# T15_PRI_SYS_V1_3.net
KiCad netlist of a schematic drawn in EAGLE
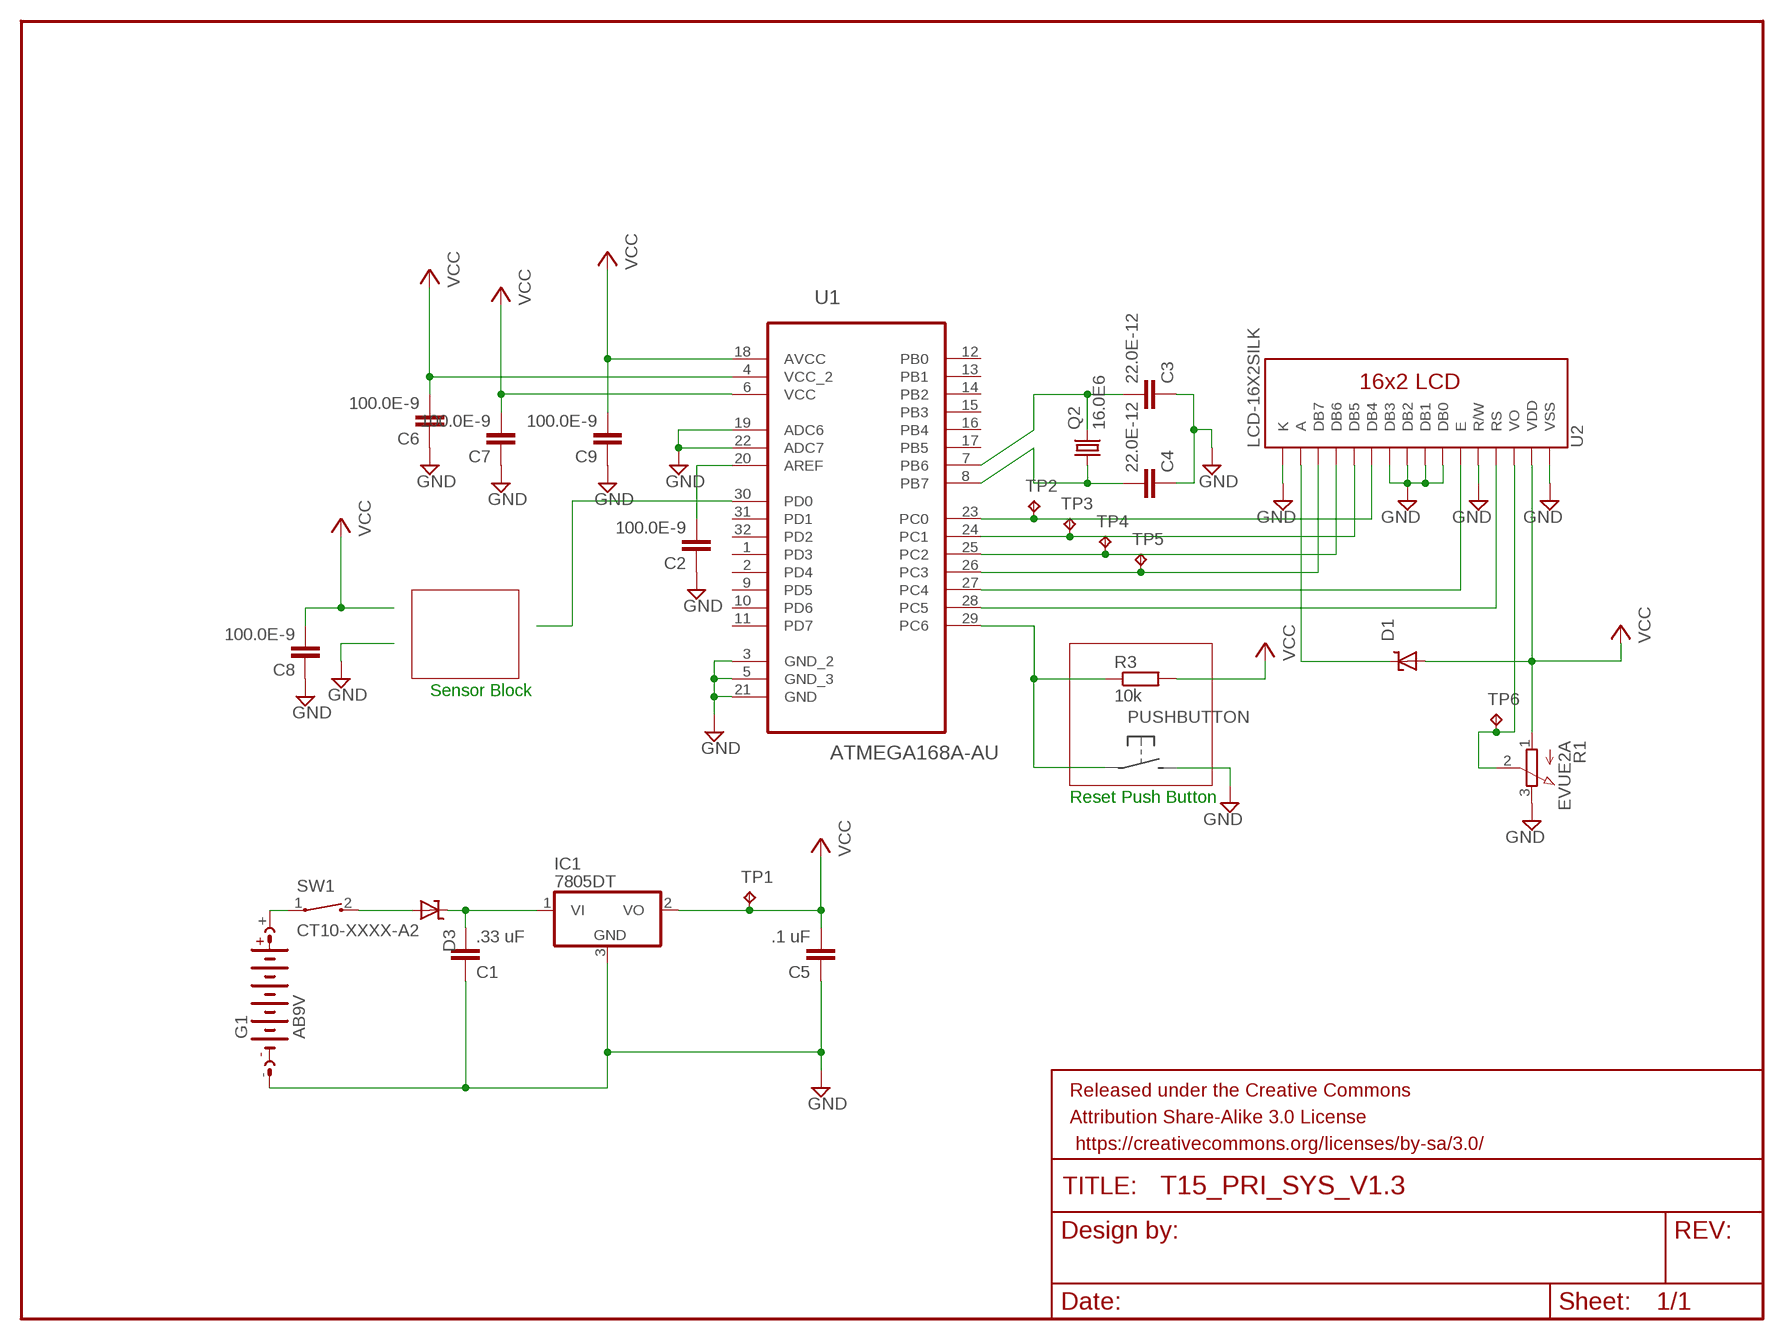
[diagram p0: schematic, sheet 1]

(export (version "E")
  (design (tool "Eeschema 10.0.6"))
  (components
    (comp (ref "C1")
      (value ".33 uF")
      (footprint "eagle-import:C025-024X044")
      (libsource (lib "eagle-import") (part "C-EU025-024X044"))
    )
    (comp (ref "C2")
      (value "100.0E-9")
      (footprint "eagle-import:C025-024X044")
      (libsource (lib "eagle-import") (part "C-EU025-024X044"))
    )
    (comp (ref "C3")
      (value "22.0E-12")
      (footprint "eagle-import:C025-024X044")
      (libsource (lib "eagle-import") (part "C-EU025-024X044"))
    )
    (comp (ref "C4")
      (value "22.0E-12")
      (footprint "eagle-import:C025-024X044")
      (libsource (lib "eagle-import") (part "C-EU025-024X044"))
    )
    (comp (ref "C5")
      (value ".1 uF")
      (footprint "eagle-import:C025-024X044")
      (libsource (lib "eagle-import") (part "C-EU025-024X044"))
    )
    (comp (ref "C6")
      (value "100.0E-9")
      (footprint "eagle-import:C025-024X044")
      (libsource (lib "eagle-import") (part "C-EU025-024X044"))
    )
    (comp (ref "C7")
      (value "100.0E-9")
      (footprint "eagle-import:C025-024X044")
      (libsource (lib "eagle-import") (part "C-EU025-024X044"))
    )
    (comp (ref "C8")
      (value "100.0E-9")
      (footprint "eagle-import:C025-024X044")
      (libsource (lib "eagle-import") (part "C-EU025-024X044"))
    )
    (comp (ref "C9")
      (value "100.0E-9")
      (footprint "eagle-import:C025-024X044")
      (libsource (lib "eagle-import") (part "C-EU025-024X044"))
    )
    (comp (ref "D1")
      (value "SUPPRESSOR-SMBJ")
      (footprint "eagle-import:SMBJ")
      (libsource (lib "eagle-import") (part "SUPPRESSOR-SMBJ"))
    )
    (comp (ref "D3")
      (value "SUPPRESSOR-SMBJ")
      (footprint "eagle-import:SMBJ")
      (libsource (lib "eagle-import") (part "SUPPRESSOR-SMBJ"))
    )
    (comp (ref "FRAME1")
      (value "FRAME-LETTER")
      (footprint "eagle-import:CREATIVE_COMMONS")
      (libsource (lib "eagle-import") (part "FRAME-LETTER"))
    )
    (comp (ref "G1")
      (value "AB9V")
      (footprint "eagle-import:AB9V")
      (libsource (lib "eagle-import") (part "AB9V"))
    )
    (comp (ref "IC1")
      (value "7805DT")
      (footprint "eagle-import:TO252")
      (libsource (lib "eagle-import") (part "78DT05"))
    )
    (comp (ref "Q2")
      (value "16.0E6")
      (footprint "eagle-import:HC49_S")
      (libsource (lib "eagle-import") (part "CRYSTALHC49S"))
    )
    (comp (ref "R1")
      (value "EVUE2A")
      (footprint "eagle-import:EVUE")
      (libsource (lib "eagle-import") (part "EVUE2A"))
    )
    (comp (ref "R3")
      (value "10k")
      (footprint "eagle-import:0204_5")
      (libsource (lib "eagle-import") (part "R-EU_0204/5"))
    )
    (comp (ref "SW1")
      (value "CT10-XXXX-A2")
      (footprint "eagle-import:CT10-XXXX-A2")
      (libsource (lib "eagle-import") (part "CT10-XXXX-A2"))
    )
    (comp (ref "TP1")
      (value "TPB1,27")
      (footprint "eagle-import:B1,27")
      (libsource (lib "eagle-import") (part "TPB1,27"))
    )
    (comp (ref "TP2")
      (value "TPB1,27")
      (footprint "eagle-import:B1,27")
      (libsource (lib "eagle-import") (part "TPB1,27"))
    )
    (comp (ref "TP3")
      (value "TPB1,27")
      (footprint "eagle-import:B1,27")
      (libsource (lib "eagle-import") (part "TPB1,27"))
    )
    (comp (ref "TP4")
      (value "TPB1,27")
      (footprint "eagle-import:B1,27")
      (libsource (lib "eagle-import") (part "TPB1,27"))
    )
    (comp (ref "TP5")
      (value "TPB1,27")
      (footprint "eagle-import:B1,27")
      (libsource (lib "eagle-import") (part "TPB1,27"))
    )
    (comp (ref "TP6")
      (value "TPB1,27")
      (footprint "eagle-import:B1,27")
      (libsource (lib "eagle-import") (part "TPB1,27"))
    )
    (comp (ref "U1")
      (value "ATMEGA168A-AU")
      (footprint "eagle-import:QFP80P900X900X120-32N")
      (libsource (lib "eagle-import") (part "ATMEGA168A-AU"))
    )
    (comp (ref "U2")
      (value "LCD-16X2SILK")
      (footprint "eagle-import:LCD-16X2")
      (libsource (lib "eagle-import") (part "LCD-16X2SILK"))
    )
  )
  (nets
    (net (code "1") (name "GND") (class "Default")
      (node (ref "C1") (pin "1") (pinfunction "1_1") (pintype "passive"))
      (node (ref "C2") (pin "1") (pinfunction "1_1") (pintype "passive"))
      (node (ref "C3") (pin "1") (pinfunction "1_1") (pintype "passive"))
      (node (ref "C4") (pin "1") (pinfunction "1_1") (pintype "passive"))
      (node (ref "C5") (pin "1") (pinfunction "1_1") (pintype "passive"))
      (node (ref "C6") (pin "1") (pinfunction "1_1") (pintype "passive"))
      (node (ref "C7") (pin "1") (pinfunction "1_1") (pintype "passive"))
      (node (ref "C8") (pin "1") (pinfunction "1_1") (pintype "passive"))
      (node (ref "C9") (pin "1") (pinfunction "1_1") (pintype "passive"))
      (node (ref "G1") (pin "-") (pinfunction "-_-") (pintype "passive"))
      (node (ref "IC1") (pin "3") (pinfunction "GND_3") (pintype "passive"))
      (node (ref "R1") (pin "3") (pinfunction "E_3") (pintype "passive"))
      (node (ref "U1") (pin "19") (pinfunction "ADC6_19") (pintype "input"))
      (node (ref "U1") (pin "21") (pinfunction "GND_21") (pintype "passive"))
      (node (ref "U1") (pin "22") (pinfunction "ADC7_22") (pintype "input"))
      (node (ref "U1") (pin "3") (pinfunction "GND_2_3") (pintype "passive"))
      (node (ref "U1") (pin "5") (pinfunction "GND_3_5") (pintype "passive"))
      (node (ref "U2") (pin "1") (pinfunction "VSS_1") (pintype "power_in"))
      (node (ref "U2") (pin "10") (pinfunction "DB3_10") (pintype "bidirectional"))
      (node (ref "U2") (pin "16") (pinfunction "K_16") (pintype "power_in"))
      (node (ref "U2") (pin "5") (pinfunction "R/W_5") (pintype "input"))
      (node (ref "U2") (pin "7") (pinfunction "DB0_7") (pintype "bidirectional"))
      (node (ref "U2") (pin "8") (pinfunction "DB1_8") (pintype "bidirectional"))
      (node (ref "U2") (pin "9") (pinfunction "DB2_9") (pintype "bidirectional"))
    )
    (net (code "2") (name "Net-(D3-PadA)") (class "Default")
      (node (ref "D3") (pin "A") (pinfunction "A_A") (pintype "passive"))
      (node (ref "SW1") (pin "2") (pinfunction "2_2") (pintype "passive"))
    )
    (net (code "3") (name "Net-(G1-Pad+)") (class "Default")
      (node (ref "G1") (pin "+") (pinfunction "+_+") (pintype "passive"))
      (node (ref "SW1") (pin "1") (pinfunction "1_1") (pintype "passive"))
    )
    (net (code "4") (name "Net-(IC1-VI)") (class "Default")
      (node (ref "C1") (pin "2") (pinfunction "2_2") (pintype "passive"))
      (node (ref "D3") (pin "C") (pinfunction "C_C") (pintype "passive"))
      (node (ref "IC1") (pin "1") (pinfunction "VI_1") (pintype "input"))
    )
    (net (code "5") (name "Net-(R1-S)") (class "Default")
      (node (ref "R1") (pin "2") (pinfunction "S_2") (pintype "passive"))
      (node (ref "TP6") (pin "TP") (pinfunction "TP_TP") (pintype "input"))
      (node (ref "U2") (pin "3") (pinfunction "VO_3") (pintype "bidirectional"))
    )
    (net (code "6") (name "Net-(U1-AREF)") (class "Default")
      (node (ref "C2") (pin "2") (pinfunction "2_2") (pintype "passive"))
      (node (ref "U1") (pin "20") (pinfunction "AREF_20") (pintype "input"))
    )
    (net (code "7") (name "Net-(U1-PB6)") (class "Default")
      (node (ref "C3") (pin "2") (pinfunction "2_2") (pintype "passive"))
      (node (ref "Q2") (pin "2") (pinfunction "2_2") (pintype "passive"))
      (node (ref "U1") (pin "7") (pinfunction "PB6_7") (pintype "bidirectional"))
    )
    (net (code "8") (name "Net-(U1-PB7)") (class "Default")
      (node (ref "C4") (pin "2") (pinfunction "2_2") (pintype "passive"))
      (node (ref "Q2") (pin "1") (pinfunction "1_1") (pintype "passive"))
      (node (ref "U1") (pin "8") (pinfunction "PB7_8") (pintype "bidirectional"))
    )
    (net (code "9") (name "Net-(U1-PC0)") (class "Default")
      (node (ref "TP2") (pin "TP") (pinfunction "TP_TP") (pintype "input"))
      (node (ref "U1") (pin "23") (pinfunction "PC0_23") (pintype "bidirectional"))
      (node (ref "U2") (pin "11") (pinfunction "DB4_11") (pintype "bidirectional"))
    )
    (net (code "10") (name "Net-(U1-PC1)") (class "Default")
      (node (ref "TP3") (pin "TP") (pinfunction "TP_TP") (pintype "input"))
      (node (ref "U1") (pin "24") (pinfunction "PC1_24") (pintype "bidirectional"))
      (node (ref "U2") (pin "12") (pinfunction "DB5_12") (pintype "bidirectional"))
    )
    (net (code "11") (name "Net-(U1-PC2)") (class "Default")
      (node (ref "TP4") (pin "TP") (pinfunction "TP_TP") (pintype "input"))
      (node (ref "U1") (pin "25") (pinfunction "PC2_25") (pintype "bidirectional"))
      (node (ref "U2") (pin "13") (pinfunction "DB6_13") (pintype "bidirectional"))
    )
    (net (code "12") (name "Net-(U1-PC3)") (class "Default")
      (node (ref "TP5") (pin "TP") (pinfunction "TP_TP") (pintype "input"))
      (node (ref "U1") (pin "26") (pinfunction "PC3_26") (pintype "bidirectional"))
      (node (ref "U2") (pin "14") (pinfunction "DB7_14") (pintype "bidirectional"))
    )
    (net (code "13") (name "Net-(U1-PC4)") (class "Default")
      (node (ref "U1") (pin "27") (pinfunction "PC4_27") (pintype "bidirectional"))
      (node (ref "U2") (pin "6") (pinfunction "E_6") (pintype "input"))
    )
    (net (code "14") (name "Net-(U1-PC5)") (class "Default")
      (node (ref "U1") (pin "28") (pinfunction "PC5_28") (pintype "bidirectional"))
      (node (ref "U2") (pin "4") (pinfunction "RS_4") (pintype "input"))
    )
    (net (code "15") (name "Net-(U1-PC6)") (class "Default")
      (node (ref "R3") (pin "1") (pinfunction "1_1") (pintype "passive"))
      (node (ref "U1") (pin "29") (pinfunction "PC6_29") (pintype "bidirectional"))
    )
    (net (code "16") (name "Net-(U2-A)") (class "Default")
      (node (ref "D1") (pin "C") (pinfunction "C_C") (pintype "passive"))
      (node (ref "U2") (pin "15") (pinfunction "A_15") (pintype "power_in"))
    )
    (net (code "17") (name "VCC") (class "Default")
      (node (ref "C5") (pin "2") (pinfunction "2_2") (pintype "passive"))
      (node (ref "C6") (pin "2") (pinfunction "2_2") (pintype "passive"))
      (node (ref "C7") (pin "2") (pinfunction "2_2") (pintype "passive"))
      (node (ref "C8") (pin "2") (pinfunction "2_2") (pintype "passive"))
      (node (ref "C9") (pin "2") (pinfunction "2_2") (pintype "passive"))
      (node (ref "D1") (pin "A") (pinfunction "A_A") (pintype "passive"))
      (node (ref "IC1") (pin "2") (pinfunction "VO_2") (pintype "passive"))
      (node (ref "R1") (pin "1") (pinfunction "A_1") (pintype "passive"))
      (node (ref "R3") (pin "2") (pinfunction "2_2") (pintype "passive"))
      (node (ref "TP1") (pin "TP") (pinfunction "TP_TP") (pintype "input"))
      (node (ref "U1") (pin "18") (pinfunction "AVCC_18") (pintype "power_in"))
      (node (ref "U1") (pin "4") (pinfunction "VCC_2_4") (pintype "power_in"))
      (node (ref "U1") (pin "6") (pinfunction "VCC_6") (pintype "power_in"))
      (node (ref "U2") (pin "2") (pinfunction "VDD_2") (pintype "power_in"))
    )
    (net (code "18") (name "unconnected-(U1-PB0-Pad12)") (class "Default")
      (node (ref "U1") (pin "12") (pinfunction "PB0_12") (pintype "bidirectional"))
    )
    (net (code "19") (name "unconnected-(U1-PB1-Pad13)") (class "Default")
      (node (ref "U1") (pin "13") (pinfunction "PB1_13") (pintype "bidirectional"))
    )
    (net (code "20") (name "unconnected-(U1-PB2-Pad14)") (class "Default")
      (node (ref "U1") (pin "14") (pinfunction "PB2_14") (pintype "bidirectional"))
    )
    (net (code "21") (name "unconnected-(U1-PB3-Pad15)") (class "Default")
      (node (ref "U1") (pin "15") (pinfunction "PB3_15") (pintype "bidirectional"))
    )
    (net (code "22") (name "unconnected-(U1-PB4-Pad16)") (class "Default")
      (node (ref "U1") (pin "16") (pinfunction "PB4_16") (pintype "bidirectional"))
    )
    (net (code "23") (name "unconnected-(U1-PB5-Pad17)") (class "Default")
      (node (ref "U1") (pin "17") (pinfunction "PB5_17") (pintype "bidirectional"))
    )
    (net (code "24") (name "unconnected-(U1-PD0-Pad30)") (class "Default")
      (node (ref "U1") (pin "30") (pinfunction "PD0_30") (pintype "bidirectional"))
    )
    (net (code "25") (name "unconnected-(U1-PD1-Pad31)") (class "Default")
      (node (ref "U1") (pin "31") (pinfunction "PD1_31") (pintype "bidirectional"))
    )
    (net (code "26") (name "unconnected-(U1-PD2-Pad32)") (class "Default")
      (node (ref "U1") (pin "32") (pinfunction "PD2_32") (pintype "bidirectional"))
    )
    (net (code "27") (name "unconnected-(U1-PD3-Pad1)") (class "Default")
      (node (ref "U1") (pin "1") (pinfunction "PD3_1") (pintype "bidirectional"))
    )
    (net (code "28") (name "unconnected-(U1-PD4-Pad2)") (class "Default")
      (node (ref "U1") (pin "2") (pinfunction "PD4_2") (pintype "bidirectional"))
    )
    (net (code "29") (name "unconnected-(U1-PD5-Pad9)") (class "Default")
      (node (ref "U1") (pin "9") (pinfunction "PD5_9") (pintype "bidirectional"))
    )
    (net (code "30") (name "unconnected-(U1-PD6-Pad10)") (class "Default")
      (node (ref "U1") (pin "10") (pinfunction "PD6_10") (pintype "bidirectional"))
    )
    (net (code "31") (name "unconnected-(U1-PD7-Pad11)") (class "Default")
      (node (ref "U1") (pin "11") (pinfunction "PD7_11") (pintype "bidirectional"))
    )
  )
)
